# STM32-PROX_5.net
KiCad netlist of a schematic drawn in Altium Designer
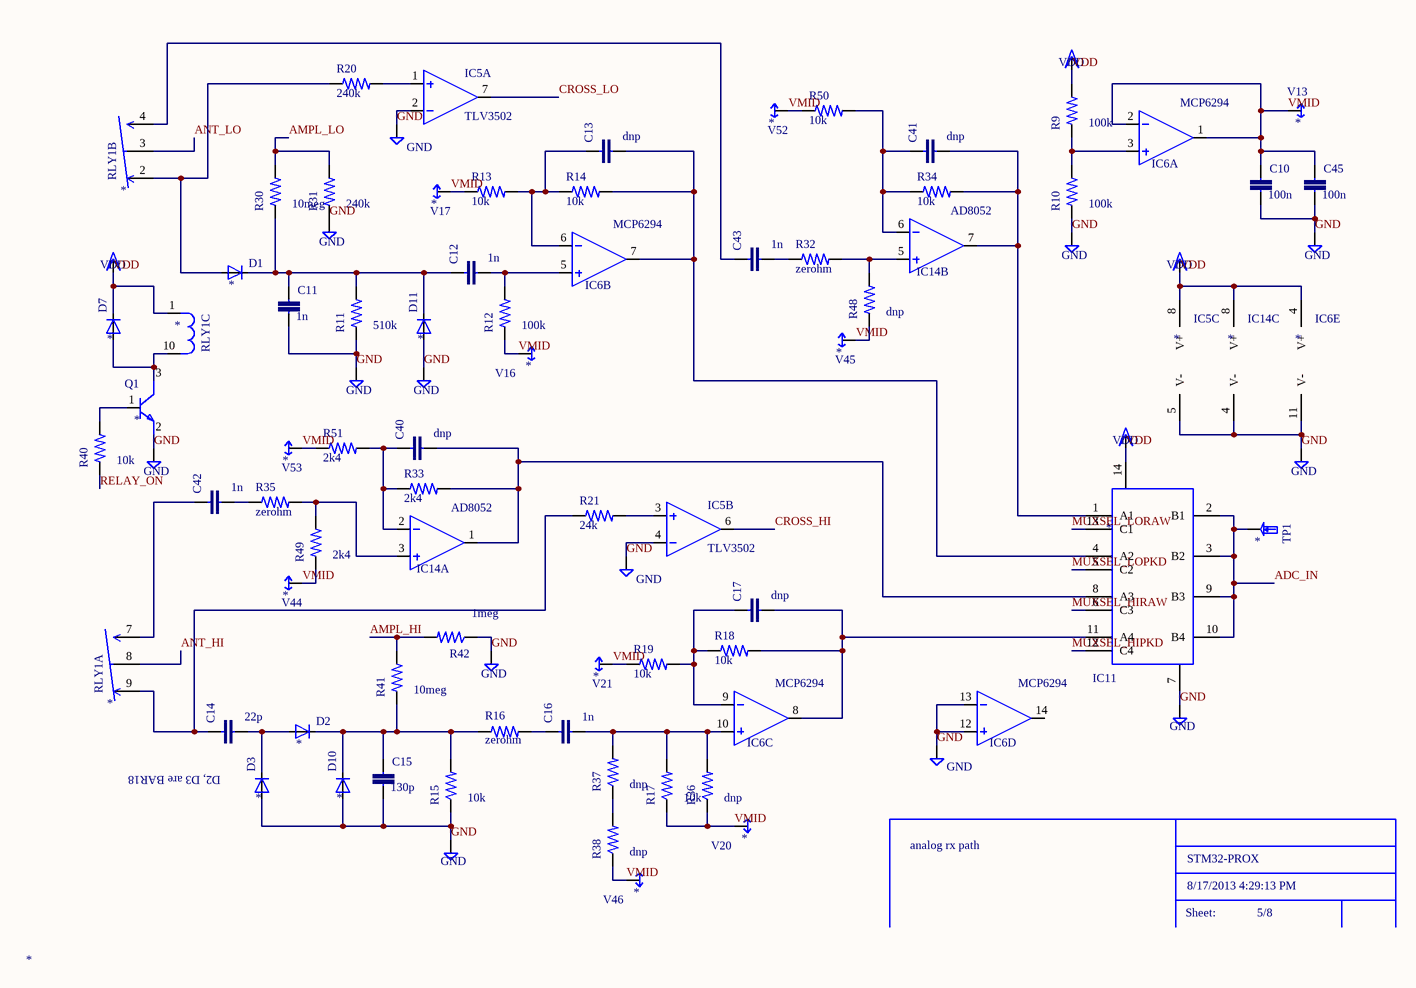
[diagram p0: STM32-PROX_5.SchDoc]

(export (version "E")
  (design (tool "Eeschema 10.0.6"))
  (components
    (comp (ref "C10") (value "100n") (footprint "RLC_0603") (libsource (lib "") (part "CAPACITOR0603_1")))
    (comp (ref "C11") (value "1n") (footprint "RLC_0603") (libsource (lib "") (part "CAPACITOR0603_1")))
    (comp (ref "C12") (value "1n") (footprint "RLC_0603") (libsource (lib "merged") (part "CAPACITOR0603")))
    (comp (ref "C13") (value "dnp") (footprint "RLC_0603") (libsource (lib "merged") (part "CAPACITOR0603")))
    (comp (ref "C14") (value "22p") (footprint "RLC_0603") (libsource (lib "merged") (part "CAPACITOR0603")))
    (comp (ref "C15") (value "130p") (footprint "RLC_0603") (libsource (lib "") (part "CAPACITOR0603_1")))
    (comp (ref "C16") (value "1n") (footprint "RLC_0603") (libsource (lib "merged") (part "CAPACITOR0603")))
    (comp (ref "C17") (value "dnp") (footprint "RLC_0603") (libsource (lib "merged") (part "CAPACITOR0603")))
    (comp (ref "C40") (value "dnp") (footprint "RLC_0603") (libsource (lib "merged") (part "CAPACITOR0603")))
    (comp (ref "C41") (value "dnp") (footprint "RLC_0603") (libsource (lib "merged") (part "CAPACITOR0603")))
    (comp (ref "C42") (value "1n") (footprint "RLC_0603") (libsource (lib "merged") (part "CAPACITOR0603")))
    (comp (ref "C43") (value "1n") (footprint "RLC_0603") (libsource (lib "merged") (part "CAPACITOR0603")))
    (comp (ref "C45") (value "100n") (footprint "RLC_0603") (libsource (lib "") (part "CAPACITOR0603_1")))
    (comp (ref "D1")
      (value "*")
      (footprint "SOT23-3LEAD")
      (libsource (lib "merged") (part "DIODE-SMD-SOT23"))
    )
    (comp (ref "D2")
      (value "*")
      (footprint "SOT23-3LEAD")
      (libsource (lib "merged") (part "DIODE-SMD-SOT23"))
    )
    (comp (ref "D3")
      (value "*")
      (footprint "SOT23-3LEAD")
      (libsource (lib "merged") (part "DIODE-SMD-SOT23"))
    )
    (comp (ref "D7")
      (value "*")
      (footprint "SOT23-3LEAD")
      (libsource (lib "merged") (part "DIODE-SMD-SOT23"))
    )
    (comp (ref "D10")
      (value "*")
      (footprint "SOT23-3LEAD")
      (libsource (lib "merged") (part "DIODE-SMD-SOT23"))
    )
    (comp (ref "D11")
      (value "*")
      (footprint "SOT23-3LEAD")
      (libsource (lib "merged") (part "DIODE-SMD-SOT23"))
    )
    (comp (ref "FRAME4") (value "*") (libsource (lib "frames") (part "A4L-LOC")))
    (comp (ref "IC5")
      (value "TLV3502")
      (footprint "SOT-23-8-OR-MSOP-8")
      (libsource (lib "merged") (part "COMP-TLV3502SOT-23-8-OR-MSOP-8"))
    )
    (comp (ref "IC6") (value "MCP6294") (footprint "TSSOP-14") (libsource (lib "") (part "OPAMP-TLC2274_1")))
    (comp (ref "IC11") (value "*") (footprint "TSSOP-14") (libsource (lib "merged") (part "CD4066")))
    (comp (ref "IC14") (value "AD8052") (footprint "MSOP8") (libsource (lib "") (part "OPAMP-AD8052_2")))
    (comp (ref "Q1")
      (value "*")
      (footprint "SOT23-3LEAD")
      (libsource (lib "merged") (part "NPN-SOT23-2N3904"))
    )
    (comp (ref "R9") (value "100k") (footprint "RLC_0603") (libsource (lib "merged") (part "RESISTOR0603")))
    (comp (ref "R10") (value "100k") (footprint "RLC_0603") (libsource (lib "merged") (part "RESISTOR0603")))
    (comp (ref "R11") (value "510k") (footprint "RLC_0603") (libsource (lib "merged") (part "RESISTOR0603")))
    (comp (ref "R12") (value "100k") (footprint "RLC_0603") (libsource (lib "merged") (part "RESISTOR0603")))
    (comp (ref "R13") (value "10k") (footprint "RLC_0603") (libsource (lib "merged") (part "RESISTOR0603")))
    (comp (ref "R14") (value "10k") (footprint "RLC_0603") (libsource (lib "merged") (part "RESISTOR0603")))
    (comp (ref "R15") (value "10k") (footprint "RLC_0603") (libsource (lib "") (part "RESISTOR0603_1")))
    (comp (ref "R16")
      (value "zerohm")
      (footprint "RLC_0603")
      (libsource (lib "merged") (part "RESISTOR0603"))
    )
    (comp (ref "R17") (value "10k") (footprint "RLC_0603") (libsource (lib "") (part "RESISTOR0603_1")))
    (comp (ref "R18") (value "10k") (footprint "RLC_0603") (libsource (lib "merged") (part "RESISTOR0603")))
    (comp (ref "R19") (value "10k") (footprint "RLC_0603") (libsource (lib "merged") (part "RESISTOR0603")))
    (comp (ref "R20") (value "240k") (footprint "RLC_0603") (libsource (lib "merged") (part "RESISTOR0603")))
    (comp (ref "R21") (value "24k") (footprint "RLC_0603") (libsource (lib "merged") (part "RESISTOR0603")))
    (comp (ref "R30") (value "10meg") (footprint "RLC_0603") (libsource (lib "merged") (part "RESISTOR0603")))
    (comp (ref "R31") (value "240k") (footprint "RLC_0603") (libsource (lib "merged") (part "RESISTOR0603")))
    (comp (ref "R32")
      (value "zerohm")
      (footprint "RLC_0603")
      (libsource (lib "merged") (part "RESISTOR0603"))
    )
    (comp (ref "R33") (value "2k4") (footprint "RLC_0603") (libsource (lib "merged") (part "RESISTOR0603")))
    (comp (ref "R34") (value "10k") (footprint "RLC_0603") (libsource (lib "merged") (part "RESISTOR0603")))
    (comp (ref "R35")
      (value "zerohm")
      (footprint "RLC_0603")
      (libsource (lib "merged") (part "RESISTOR0603"))
    )
    (comp (ref "R36") (value "dnp") (footprint "RLC_0603") (libsource (lib "") (part "RESISTOR0603_1")))
    (comp (ref "R37") (value "dnp") (footprint "RLC_0603") (libsource (lib "") (part "RESISTOR0603_1")))
    (comp (ref "R38") (value "dnp") (footprint "RLC_0603") (libsource (lib "") (part "RESISTOR0603_1")))
    (comp (ref "R40") (value "10k") (footprint "RLC_0603") (libsource (lib "merged") (part "RESISTOR0603")))
    (comp (ref "R41") (value "10meg") (footprint "RLC_0603") (libsource (lib "merged") (part "RESISTOR0603")))
    (comp (ref "R42") (value "1meg") (footprint "RLC_0603") (libsource (lib "") (part "RESISTOR0603_1")))
    (comp (ref "R48") (value "dnp") (footprint "RLC_0603") (libsource (lib "merged") (part "RESISTOR0603")))
    (comp (ref "R49") (value "2k4") (footprint "RLC_0603") (libsource (lib "merged") (part "RESISTOR0603")))
    (comp (ref "R50") (value "10k") (footprint "RLC_0603") (libsource (lib "merged") (part "RESISTOR0603")))
    (comp (ref "R51") (value "2k4") (footprint "RLC_0603") (libsource (lib "merged") (part "RESISTOR0603")))
    (comp (ref "RLY1") (value "*") (footprint "TQ-SMD-RELAY") (libsource (lib "") (part "RELAY-DPDT_2")))
    (comp (ref "TP1")
      (value "*")
      (footprint "KEYSTONE-SMD-TESTPOINT-5015")
      (libsource (lib "merged") (part "TESTPADKEYSTONE-SMD"))
    )
    (comp (ref "V13") (value "*") (libsource (lib "merged") (part "SUPPLY_VMID")))
    (comp (ref "V14") (value "GND") (libsource (lib "supply2") (part "GND")))
    (comp (ref "V15") (value "GND") (libsource (lib "supply2") (part "GND")))
    (comp (ref "V16") (value "*") (libsource (lib "") (part "SUPPLY_VMID_3")))
    (comp (ref "V17") (value "*") (libsource (lib "") (part "SUPPLY_VMID_2")))
    (comp (ref "V18") (value "GND") (libsource (lib "supply2") (part "GND")))
    (comp (ref "V19") (value "GND") (libsource (lib "supply2") (part "GND")))
    (comp (ref "V20") (value "*") (libsource (lib "") (part "SUPPLY_VMID_1")))
    (comp (ref "V21") (value "*") (libsource (lib "") (part "SUPPLY_VMID_2")))
    (comp (ref "V22") (value "GND") (libsource (lib "supply2") (part "GND")))
    (comp (ref "V23") (value "GND") (libsource (lib "supply2") (part "GND")))
    (comp (ref "V33") (value "GND") (libsource (lib "supply2") (part "GND")))
    (comp (ref "V34") (value "GND") (libsource (lib "supply2") (part "GND")))
    (comp (ref "V42") (value "GND") (libsource (lib "supply2") (part "GND")))
    (comp (ref "V43") (value "GND") (libsource (lib "supply2") (part "GND")))
    (comp (ref "V44") (value "*") (libsource (lib "") (part "SUPPLY_VMID_2")))
    (comp (ref "V45") (value "*") (libsource (lib "") (part "SUPPLY_VMID_2")))
    (comp (ref "V46") (value "*") (libsource (lib "") (part "SUPPLY_VMID_1")))
    (comp (ref "V48") (value "GND") (libsource (lib "supply2") (part "GND")))
    (comp (ref "V49") (value "GND") (libsource (lib "supply2") (part "GND")))
    (comp (ref "V52") (value "*") (libsource (lib "") (part "SUPPLY_VMID_2")))
    (comp (ref "V53") (value "*") (libsource (lib "") (part "SUPPLY_VMID_2")))
    (comp (ref "V56") (value "GND") (libsource (lib "supply2") (part "GND")))
    (comp (ref "VDD2") (value "VDD") (libsource (lib "supply1") (part "VDD")))
    (comp (ref "VDD3") (value "VDD") (libsource (lib "supply1") (part "VDD")))
    (comp (ref "VDD8") (value "VDD") (libsource (lib "supply1") (part "VDD")))
    (comp (ref "VDD9") (value "VDD") (libsource (lib "supply1") (part "VDD")))
  )
  (nets
    (net (code "1") (name "/ADC_IN") (class "Default")
      (node (ref "IC11") (pin "10") (pinfunction "B4_10") (pintype "passive"))
      (node (ref "IC11") (pin "2") (pinfunction "B1_2") (pintype "passive"))
      (node (ref "IC11") (pin "3") (pinfunction "B2_3") (pintype "passive"))
      (node (ref "IC11") (pin "9") (pinfunction "B3_9") (pintype "passive"))
      (node (ref "TP1") (pin "1") (pinfunction "P$1_1") (pintype "passive"))
    )
    (net (code "2") (name "/AMPL_HI") (class "Default")
      (node (ref "R41") (pin "2") (pinfunction "2_2") (pintype "passive"))
      (node (ref "R42") (pin "2") (pinfunction "2_2") (pintype "passive"))
    )
    (net (code "3") (name "/AMPL_LO") (class "Default")
      (node (ref "R30") (pin "2") (pinfunction "2_2") (pintype "passive"))
      (node (ref "R31") (pin "2") (pinfunction "2_2") (pintype "passive"))
    )
    (net (code "4") (name "/ANT_HI") (class "Default")
      (node (ref "RLY1") (pin "8") (pinfunction "COM_8") (pintype "passive"))
    )
    (net (code "5") (name "/ANT_LO") (class "Default")
      (node (ref "RLY1") (pin "3") (pinfunction "COM_3") (pintype "passive"))
    )
    (net (code "6") (name "/CROSS_HI") (class "Default")
      (node (ref "IC5") (pin "6") (pinfunction "OUT_6") (pintype "passive"))
    )
    (net (code "7") (name "/CROSS_LO") (class "Default")
      (node (ref "IC5") (pin "7") (pinfunction "OUT_7") (pintype "passive"))
    )
    (net (code "8") (name "/GND") (class "Default")
      (node (ref "C10") (pin "2") (pinfunction "2_2") (pintype "passive"))
      (node (ref "C11") (pin "2") (pinfunction "2_2") (pintype "passive"))
      (node (ref "C15") (pin "2") (pinfunction "2_2") (pintype "passive"))
      (node (ref "C45") (pin "2") (pinfunction "2_2") (pintype "passive"))
      (node (ref "D10") (pin "1") (pinfunction "A_1") (pintype "passive"))
      (node (ref "D11") (pin "1") (pinfunction "A_1") (pintype "passive"))
      (node (ref "D3") (pin "1") (pinfunction "A_1") (pintype "passive"))
      (node (ref "IC11") (pin "7") (pinfunction "VSS_7") (pintype "passive"))
      (node (ref "IC14") (pin "4") (pinfunction "V-_4") (pintype "passive"))
      (node (ref "IC5") (pin "2") (pinfunction "-IN_2") (pintype "passive"))
      (node (ref "IC5") (pin "4") (pinfunction "-IN_4") (pintype "passive"))
      (node (ref "IC5") (pin "5") (pinfunction "V-_5") (pintype "passive"))
      (node (ref "IC6") (pin "11") (pinfunction "V-_11") (pintype "passive"))
      (node (ref "IC6") (pin "12") (pinfunction "+IN_12") (pintype "passive"))
      (node (ref "IC6") (pin "13") (pinfunction "-IN_13") (pintype "passive"))
      (node (ref "Q1") (pin "2") (pinfunction "E_2") (pintype "passive"))
      (node (ref "R10") (pin "1") (pinfunction "1_1") (pintype "passive"))
      (node (ref "R11") (pin "1") (pinfunction "1_1") (pintype "passive"))
      (node (ref "R15") (pin "1") (pinfunction "1_1") (pintype "passive"))
      (node (ref "R31") (pin "1") (pinfunction "1_1") (pintype "passive"))
      (node (ref "R42") (pin "1") (pinfunction "1_1") (pintype "passive"))
      (node (ref "V14") (pin "0") (pinfunction "GND_0") (pintype "passive"))
      (node (ref "V15") (pin "0") (pinfunction "GND_0") (pintype "passive"))
      (node (ref "V18") (pin "0") (pinfunction "GND_0") (pintype "passive"))
      (node (ref "V19") (pin "0") (pinfunction "GND_0") (pintype "passive"))
      (node (ref "V22") (pin "0") (pinfunction "GND_0") (pintype "passive"))
      (node (ref "V23") (pin "0") (pinfunction "GND_0") (pintype "passive"))
      (node (ref "V33") (pin "0") (pinfunction "GND_0") (pintype "passive"))
      (node (ref "V34") (pin "0") (pinfunction "GND_0") (pintype "passive"))
      (node (ref "V42") (pin "0") (pinfunction "GND_0") (pintype "passive"))
      (node (ref "V43") (pin "0") (pinfunction "GND_0") (pintype "passive"))
      (node (ref "V48") (pin "0") (pinfunction "GND_0") (pintype "passive"))
      (node (ref "V49") (pin "0") (pinfunction "GND_0") (pintype "passive"))
      (node (ref "V56") (pin "0") (pinfunction "GND_0") (pintype "passive"))
    )
    (net (code "9") (name "/MUXSEL_HIPKD") (class "Default")
      (node (ref "IC11") (pin "12") (pinfunction "C4_12") (pintype "passive"))
    )
    (net (code "10") (name "/MUXSEL_HIRAW") (class "Default")
      (node (ref "IC11") (pin "6") (pinfunction "C3_6") (pintype "passive"))
    )
    (net (code "11") (name "/MUXSEL_LOPKD") (class "Default")
      (node (ref "IC11") (pin "5") (pinfunction "C2_5") (pintype "passive"))
    )
    (net (code "12") (name "/MUXSEL_LORAW") (class "Default")
      (node (ref "IC11") (pin "13") (pinfunction "C1_13") (pintype "passive"))
    )
    (net (code "13") (name "/RELAY_ON") (class "Default")
      (node (ref "R40") (pin "1") (pinfunction "1_1") (pintype "passive"))
    )
    (net (code "14") (name "/VDD") (class "Default")
      (node (ref "D7") (pin "3") (pinfunction "C_3") (pintype "passive"))
      (node (ref "IC11") (pin "14") (pinfunction "VDD_14") (pintype "passive"))
      (node (ref "IC14") (pin "8") (pinfunction "V+_8") (pintype "passive"))
      (node (ref "IC5") (pin "8") (pinfunction "V+_8") (pintype "passive"))
      (node (ref "IC6") (pin "4") (pinfunction "V+_4") (pintype "passive"))
      (node (ref "R9") (pin "2") (pinfunction "2_2") (pintype "passive"))
      (node (ref "RLY1") (pin "1") (pinfunction "P$1_1") (pintype "passive"))
      (node (ref "VDD2") (pin "0") (pinfunction "VDD_0") (pintype "passive"))
      (node (ref "VDD3") (pin "0") (pinfunction "VDD_0") (pintype "passive"))
      (node (ref "VDD8") (pin "0") (pinfunction "VDD_0") (pintype "passive"))
      (node (ref "VDD9") (pin "0") (pinfunction "VDD_0") (pintype "passive"))
    )
    (net (code "15") (name "/VMID") (class "Default")
      (node (ref "C10") (pin "1") (pinfunction "1_1") (pintype "passive"))
      (node (ref "C45") (pin "1") (pinfunction "1_1") (pintype "passive"))
      (node (ref "IC6") (pin "1") (pinfunction "OUT_1") (pintype "passive"))
      (node (ref "IC6") (pin "2") (pinfunction "-IN_2") (pintype "passive"))
      (node (ref "R12") (pin "1") (pinfunction "1_1") (pintype "passive"))
      (node (ref "R13") (pin "1") (pinfunction "1_1") (pintype "passive"))
      (node (ref "R17") (pin "1") (pinfunction "1_1") (pintype "passive"))
      (node (ref "R19") (pin "1") (pinfunction "1_1") (pintype "passive"))
      (node (ref "R36") (pin "1") (pinfunction "1_1") (pintype "passive"))
      (node (ref "R38") (pin "1") (pinfunction "1_1") (pintype "passive"))
      (node (ref "R48") (pin "1") (pinfunction "1_1") (pintype "passive"))
      (node (ref "R49") (pin "1") (pinfunction "1_1") (pintype "passive"))
      (node (ref "R50") (pin "1") (pinfunction "1_1") (pintype "passive"))
      (node (ref "R51") (pin "1") (pinfunction "1_1") (pintype "passive"))
      (node (ref "V13") (pin "0") (pinfunction "VMID_0") (pintype "passive"))
      (node (ref "V16") (pin "0") (pinfunction "VMID_0") (pintype "passive"))
      (node (ref "V17") (pin "0") (pinfunction "VMID_0") (pintype "passive"))
      (node (ref "V20") (pin "0") (pinfunction "VMID_0") (pintype "passive"))
      (node (ref "V21") (pin "0") (pinfunction "VMID_0") (pintype "passive"))
      (node (ref "V44") (pin "0") (pinfunction "VMID_0") (pintype "passive"))
      (node (ref "V45") (pin "0") (pinfunction "VMID_0") (pintype "passive"))
      (node (ref "V46") (pin "0") (pinfunction "VMID_0") (pintype "passive"))
      (node (ref "V52") (pin "0") (pinfunction "VMID_0") (pintype "passive"))
      (node (ref "V53") (pin "0") (pinfunction "VMID_0") (pintype "passive"))
    )
    (net (code "16") (name "Net-(C16-Pad1)") (class "Default")
      (node (ref "C16") (pin "1") (pinfunction "1_1") (pintype "passive"))
      (node (ref "R16") (pin "2") (pinfunction "2_2") (pintype "passive"))
    )
    (net (code "17") (name "Net-(C42-Pad2)") (class "Default")
      (node (ref "C42") (pin "2") (pinfunction "2_2") (pintype "passive"))
      (node (ref "R35") (pin "1") (pinfunction "1_1") (pintype "passive"))
    )
    (net (code "18") (name "Net-(C43-Pad2)") (class "Default")
      (node (ref "C43") (pin "2") (pinfunction "2_2") (pintype "passive"))
      (node (ref "R32") (pin "1") (pinfunction "1_1") (pintype "passive"))
    )
    (net (code "19") (name "Net-(D1-A)") (class "Default")
      (node (ref "D1") (pin "1") (pinfunction "A_1") (pintype "passive"))
      (node (ref "R20") (pin "1") (pinfunction "1_1") (pintype "passive"))
      (node (ref "RLY1") (pin "2") (pinfunction "NC_2") (pintype "passive"))
    )
    (net (code "20") (name "Net-(D1-C)") (class "Default")
      (node (ref "C11") (pin "1") (pinfunction "1_1") (pintype "passive"))
      (node (ref "C12") (pin "1") (pinfunction "1_1") (pintype "passive"))
      (node (ref "D1") (pin "3") (pinfunction "C_3") (pintype "passive"))
      (node (ref "D11") (pin "3") (pinfunction "C_3") (pintype "passive"))
      (node (ref "R11") (pin "2") (pinfunction "2_2") (pintype "passive"))
      (node (ref "R30") (pin "1") (pinfunction "1_1") (pintype "passive"))
    )
    (net (code "21") (name "Net-(D2-A)") (class "Default")
      (node (ref "C14") (pin "2") (pinfunction "2_2") (pintype "passive"))
      (node (ref "D2") (pin "1") (pinfunction "A_1") (pintype "passive"))
      (node (ref "D3") (pin "3") (pinfunction "C_3") (pintype "passive"))
    )
    (net (code "22") (name "Net-(D7-A)") (class "Default")
      (node (ref "D7") (pin "1") (pinfunction "A_1") (pintype "passive"))
      (node (ref "Q1") (pin "3") (pinfunction "C_3") (pintype "passive"))
      (node (ref "RLY1") (pin "10") (pinfunction "P$2_10") (pintype "passive"))
    )
    (net (code "23") (name "Net-(D10-C)") (class "Default")
      (node (ref "C15") (pin "1") (pinfunction "1_1") (pintype "passive"))
      (node (ref "D10") (pin "3") (pinfunction "C_3") (pintype "passive"))
      (node (ref "D2") (pin "3") (pinfunction "C_3") (pintype "passive"))
      (node (ref "R15") (pin "2") (pinfunction "2_2") (pintype "passive"))
      (node (ref "R16") (pin "1") (pinfunction "1_1") (pintype "passive"))
      (node (ref "R41") (pin "1") (pinfunction "1_1") (pintype "passive"))
    )
    (net (code "24") (name "Net-(IC5A-+IN)") (class "Default")
      (node (ref "IC5") (pin "1") (pinfunction "+IN_1") (pintype "passive"))
      (node (ref "R20") (pin "2") (pinfunction "2_2") (pintype "passive"))
    )
    (net (code "25") (name "Net-(IC5B-+IN)") (class "Default")
      (node (ref "IC5") (pin "3") (pinfunction "+IN_3") (pintype "passive"))
      (node (ref "R21") (pin "2") (pinfunction "2_2") (pintype "passive"))
    )
    (net (code "26") (name "Net-(IC6A-+IN)") (class "Default")
      (node (ref "IC6") (pin "3") (pinfunction "+IN_3") (pintype "passive"))
      (node (ref "R10") (pin "2") (pinfunction "2_2") (pintype "passive"))
      (node (ref "R9") (pin "1") (pinfunction "1_1") (pintype "passive"))
    )
    (net (code "27") (name "Net-(IC6B-+IN)") (class "Default")
      (node (ref "C12") (pin "2") (pinfunction "2_2") (pintype "passive"))
      (node (ref "IC6") (pin "5") (pinfunction "+IN_5") (pintype "passive"))
      (node (ref "R12") (pin "2") (pinfunction "2_2") (pintype "passive"))
    )
    (net (code "28") (name "Net-(IC6B--IN)") (class "Default")
      (node (ref "C13") (pin "1") (pinfunction "1_1") (pintype "passive"))
      (node (ref "IC6") (pin "6") (pinfunction "-IN_6") (pintype "passive"))
      (node (ref "R13") (pin "2") (pinfunction "2_2") (pintype "passive"))
      (node (ref "R14") (pin "1") (pinfunction "1_1") (pintype "passive"))
    )
    (net (code "29") (name "Net-(IC6C-+IN)") (class "Default")
      (node (ref "C16") (pin "2") (pinfunction "2_2") (pintype "passive"))
      (node (ref "IC6") (pin "10") (pinfunction "+IN_10") (pintype "passive"))
      (node (ref "R17") (pin "2") (pinfunction "2_2") (pintype "passive"))
      (node (ref "R36") (pin "2") (pinfunction "2_2") (pintype "passive"))
      (node (ref "R37") (pin "2") (pinfunction "2_2") (pintype "passive"))
    )
    (net (code "30") (name "Net-(IC6C--IN)") (class "Default")
      (node (ref "C17") (pin "1") (pinfunction "1_1") (pintype "passive"))
      (node (ref "IC6") (pin "9") (pinfunction "-IN_9") (pintype "passive"))
      (node (ref "R18") (pin "1") (pinfunction "1_1") (pintype "passive"))
      (node (ref "R19") (pin "2") (pinfunction "2_2") (pintype "passive"))
    )
    (net (code "31") (name "Net-(IC11-A1)") (class "Default")
      (node (ref "C41") (pin "2") (pinfunction "2_2") (pintype "passive"))
      (node (ref "IC11") (pin "1") (pinfunction "A1_1") (pintype "passive"))
      (node (ref "IC14") (pin "7") (pinfunction "OUT_7") (pintype "passive"))
      (node (ref "R34") (pin "2") (pinfunction "2_2") (pintype "passive"))
    )
    (net (code "32") (name "Net-(IC11-A2)") (class "Default")
      (node (ref "C13") (pin "2") (pinfunction "2_2") (pintype "passive"))
      (node (ref "IC11") (pin "4") (pinfunction "A2_4") (pintype "passive"))
      (node (ref "IC6") (pin "7") (pinfunction "OUT_7") (pintype "passive"))
      (node (ref "R14") (pin "2") (pinfunction "2_2") (pintype "passive"))
    )
    (net (code "33") (name "Net-(IC11-A3)") (class "Default")
      (node (ref "C40") (pin "2") (pinfunction "2_2") (pintype "passive"))
      (node (ref "IC11") (pin "8") (pinfunction "A3_8") (pintype "passive"))
      (node (ref "IC14") (pin "1") (pinfunction "OUT_1") (pintype "passive"))
      (node (ref "R33") (pin "2") (pinfunction "2_2") (pintype "passive"))
    )
    (net (code "34") (name "Net-(IC11-A4)") (class "Default")
      (node (ref "C17") (pin "2") (pinfunction "2_2") (pintype "passive"))
      (node (ref "IC11") (pin "11") (pinfunction "A4_11") (pintype "passive"))
      (node (ref "IC6") (pin "8") (pinfunction "OUT_8") (pintype "passive"))
      (node (ref "R18") (pin "2") (pinfunction "2_2") (pintype "passive"))
    )
    (net (code "35") (name "Net-(IC14A-+IN)") (class "Default")
      (node (ref "IC14") (pin "3") (pinfunction "+IN_3") (pintype "passive"))
      (node (ref "R35") (pin "2") (pinfunction "2_2") (pintype "passive"))
      (node (ref "R49") (pin "2") (pinfunction "2_2") (pintype "passive"))
    )
    (net (code "36") (name "Net-(IC14A--IN)") (class "Default")
      (node (ref "C40") (pin "1") (pinfunction "1_1") (pintype "passive"))
      (node (ref "IC14") (pin "2") (pinfunction "-IN_2") (pintype "passive"))
      (node (ref "R33") (pin "1") (pinfunction "1_1") (pintype "passive"))
      (node (ref "R51") (pin "2") (pinfunction "2_2") (pintype "passive"))
    )
    (net (code "37") (name "Net-(IC14B-+IN)") (class "Default")
      (node (ref "IC14") (pin "5") (pinfunction "+IN_5") (pintype "passive"))
      (node (ref "R32") (pin "2") (pinfunction "2_2") (pintype "passive"))
      (node (ref "R48") (pin "2") (pinfunction "2_2") (pintype "passive"))
    )
    (net (code "38") (name "Net-(IC14B--IN)") (class "Default")
      (node (ref "C41") (pin "1") (pinfunction "1_1") (pintype "passive"))
      (node (ref "IC14") (pin "6") (pinfunction "-IN_6") (pintype "passive"))
      (node (ref "R34") (pin "1") (pinfunction "1_1") (pintype "passive"))
      (node (ref "R50") (pin "2") (pinfunction "2_2") (pintype "passive"))
    )
    (net (code "39") (name "Net-(Q1-B)") (class "Default")
      (node (ref "Q1") (pin "1") (pinfunction "B_1") (pintype "passive"))
      (node (ref "R40") (pin "2") (pinfunction "2_2") (pintype "passive"))
    )
    (net (code "40") (name "Net-(R37-Pad1)") (class "Default")
      (node (ref "R37") (pin "1") (pinfunction "1_1") (pintype "passive"))
      (node (ref "R38") (pin "2") (pinfunction "2_2") (pintype "passive"))
    )
    (net (code "41") (name "Net-(RLY1A-NC)") (class "Default")
      (node (ref "C14") (pin "1") (pinfunction "1_1") (pintype "passive"))
      (node (ref "R21") (pin "1") (pinfunction "1_1") (pintype "passive"))
      (node (ref "RLY1") (pin "9") (pinfunction "NC_9") (pintype "passive"))
    )
    (net (code "42") (name "Net-(RLY1A-NO)") (class "Default")
      (node (ref "C42") (pin "1") (pinfunction "1_1") (pintype "passive"))
      (node (ref "RLY1") (pin "7") (pinfunction "NO_7") (pintype "passive"))
    )
    (net (code "43") (name "Net-(RLY1B-NO)") (class "Default")
      (node (ref "C43") (pin "1") (pinfunction "1_1") (pintype "passive"))
      (node (ref "RLY1") (pin "4") (pinfunction "NO_4") (pintype "passive"))
    )
    (net (code "44") (name "unconnected-(IC6D-OUT-Pad14)") (class "Default")
      (node (ref "IC6") (pin "14") (pinfunction "OUT_14") (pintype "passive"))
    )
  )
)
